# Adafruit_SPA06-003_Temperature_Pressure_.net
KiCad netlist of a schematic drawn in EAGLE
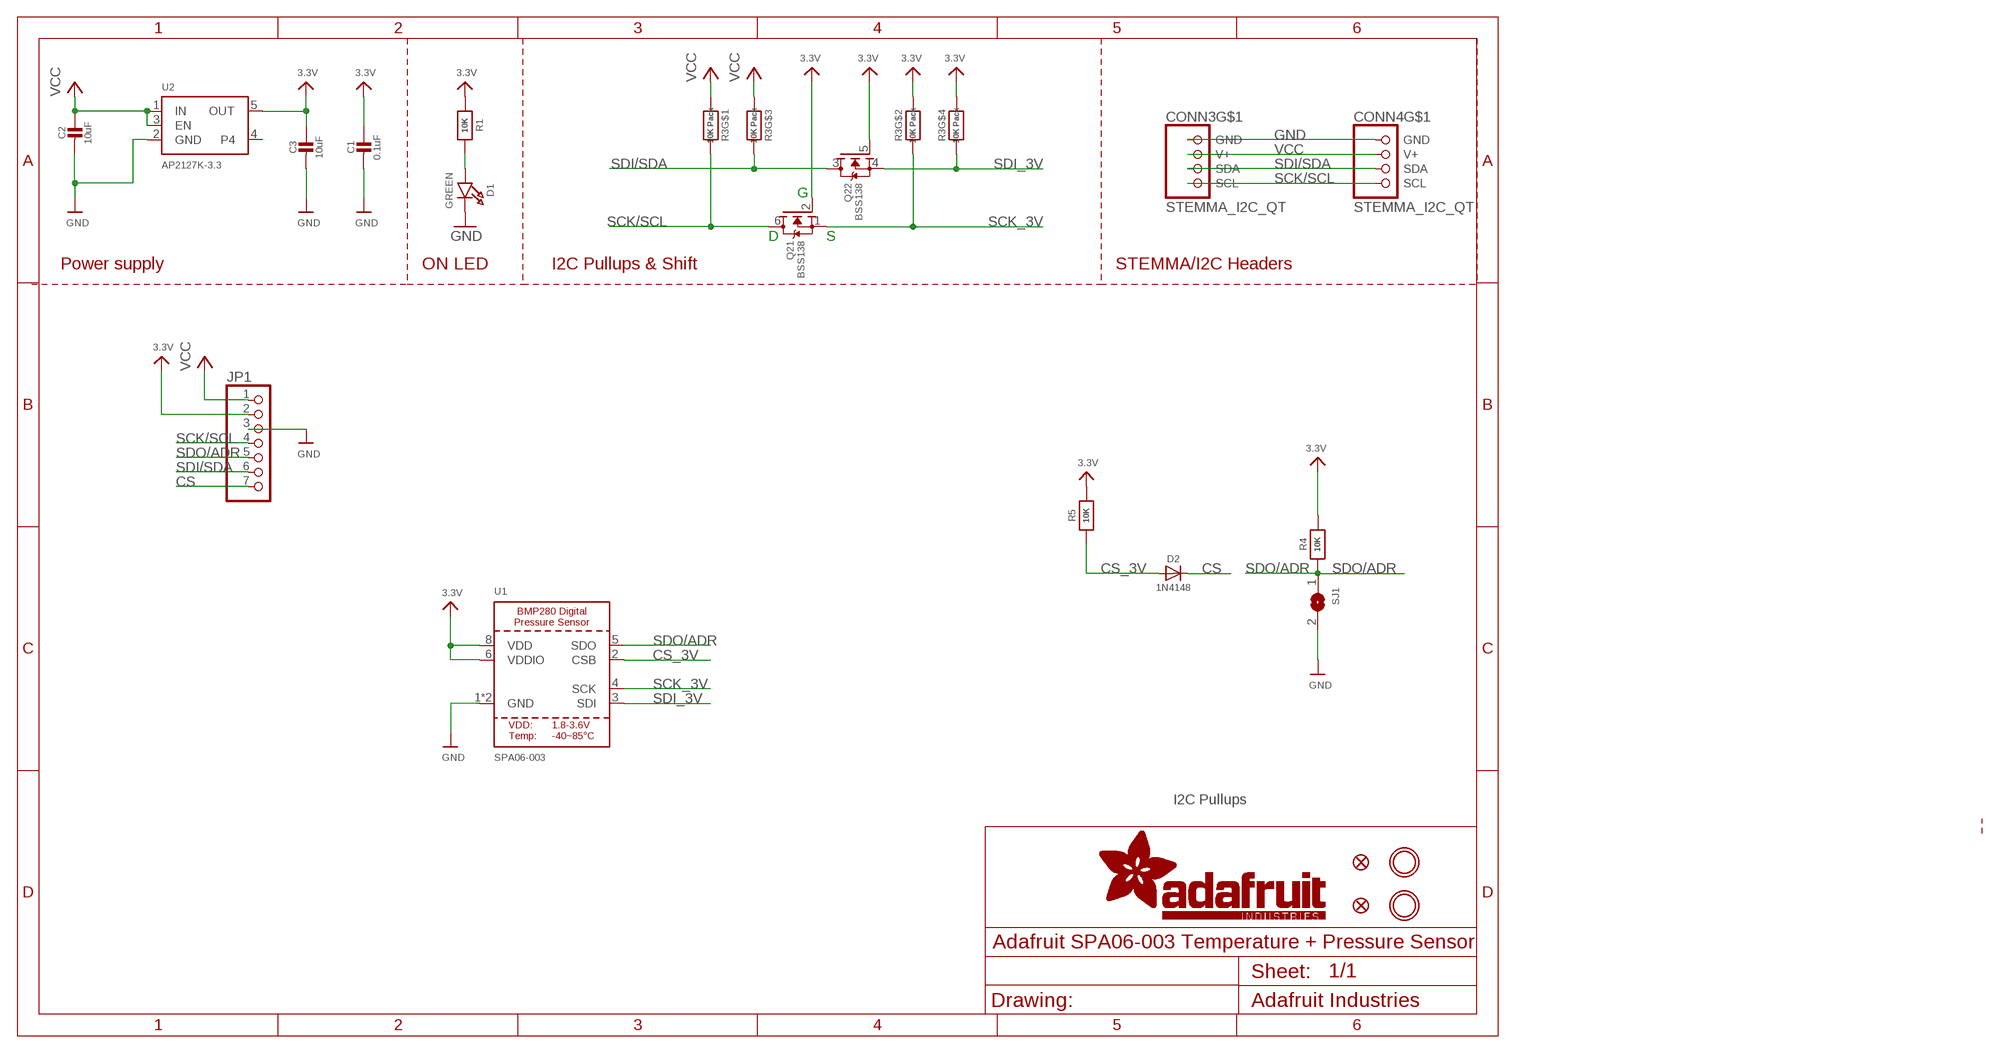
[diagram p0: schematic, sheet 1]

(export (version "E")
  (design (tool "Eeschema 10.0.6"))
  (components
    (comp (ref "C1")
      (value "0.1uF")
      (footprint "eagle-import:0603-NO")
      (libsource (lib "eagle-import") (part "CAP_CERAMIC0603_NO"))
    )
    (comp (ref "C2")
      (value "10uF")
      (footprint "eagle-import:0805-NO")
      (libsource (lib "eagle-import") (part "CAP_CERAMIC0805-NOOUTLINE"))
    )
    (comp (ref "C3")
      (value "10uF")
      (footprint "eagle-import:0805-NO")
      (libsource (lib "eagle-import") (part "CAP_CERAMIC0805-NOOUTLINE"))
    )
    (comp (ref "CONN3")
      (value "STEMMA_I2C_QT")
      (footprint "eagle-import:JST_SH4")
      (libsource (lib "eagle-import") (part "STEMMA_I2C_QT"))
    )
    (comp (ref "CONN4")
      (value "STEMMA_I2C_QT")
      (footprint "eagle-import:JST_SH4")
      (libsource (lib "eagle-import") (part "STEMMA_I2C_QT"))
    )
    (comp (ref "D1")
      (value "GREEN")
      (footprint "eagle-import:CHIPLED_0603_NOOUTLINE")
      (libsource (lib "eagle-import") (part "LED0603_NOOUTLINE"))
    )
    (comp (ref "D2")
      (value "1N4148")
      (footprint "eagle-import:SOD-323")
      (libsource (lib "eagle-import") (part "DIODESOD-323"))
    )
    (comp (ref "FID3")
      (value "FIDUCIAL_0.5MM")
      (footprint "eagle-import:FIDUCIAL_0.5MM")
      (libsource (lib "eagle-import") (part "FIDUCIAL_0.5MM"))
    )
    (comp (ref "FID4")
      (value "FIDUCIAL_0.5MM")
      (footprint "eagle-import:FIDUCIAL_0.5MM")
      (libsource (lib "eagle-import") (part "FIDUCIAL_0.5MM"))
    )
    (comp (ref "JP1")
      (value "HEADER-1X770MIL")
      (footprint "eagle-import:1X07_ROUND_70")
      (libsource (lib "eagle-import") (part "HEADER-1X770MIL"))
    )
    (comp (ref "Q2")
      (value "BSS138")
      (footprint "eagle-import:SOT363")
      (libsource (lib "eagle-import") (part "MOSFET-N_DUAL"))
    )
    (comp (ref "R1")
      (value "10K")
      (footprint "eagle-import:0603-NO")
      (libsource (lib "eagle-import") (part "RESISTOR_0603_NOOUT"))
    )
    (comp (ref "R3")
      (value "10K Pack")
      (footprint "eagle-import:RESPACK_4X0603")
      (libsource (lib "eagle-import") (part "RESISTOR_4PACK"))
    )
    (comp (ref "R4")
      (value "10K")
      (footprint "eagle-import:0603-NO")
      (libsource (lib "eagle-import") (part "RESISTOR_0603_NOOUT"))
    )
    (comp (ref "R5")
      (value "10K")
      (footprint "eagle-import:0603-NO")
      (libsource (lib "eagle-import") (part "RESISTOR_0603_NOOUT"))
    )
    (comp (ref "SJ1")
      (value "SOLDERJUMPER")
      (footprint "eagle-import:SOLDERJUMPER_ARROW_NOPASTE")
      (libsource (lib "eagle-import") (part "SOLDERJUMPER"))
    )
    (comp (ref "U$1")
      (value "MOUNTINGHOLE2.5")
      (footprint "eagle-import:MOUNTINGHOLE_2.5_PLATED")
      (libsource (lib "eagle-import") (part "MOUNTINGHOLE2.5"))
    )
    (comp (ref "U$17")
      (value "MOUNTINGHOLE2.5")
      (footprint "eagle-import:MOUNTINGHOLE_2.5_PLATED")
      (libsource (lib "eagle-import") (part "MOUNTINGHOLE2.5"))
    )
    (comp (ref "U1")
      (value "SPA06-003")
      (footprint "eagle-import:BMX280_COMBO")
      (libsource (lib "eagle-import") (part "BMP280_COMBO"))
    )
    (comp (ref "U2")
      (value "AP2127K-3.3")
      (footprint "eagle-import:SOT23-5")
      (libsource (lib "eagle-import") (part "VREG_SOT23-5"))
    )
  )
  (nets
    (net (code "1") (name "/CS") (class "Default")
      (node (ref "D2") (pin "C") (pinfunction "C_C") (pintype "passive"))
      (node (ref "JP1") (pin "7") (pinfunction "7_7") (pintype "passive"))
    )
    (net (code "2") (name "/CS_3V") (class "Default")
      (node (ref "D2") (pin "A") (pinfunction "A_A") (pintype "passive"))
      (node (ref "R5") (pin "1") (pinfunction "1_1") (pintype "passive"))
      (node (ref "U1") (pin "2") (pinfunction "CSB_2") (pintype "input"))
    )
    (net (code "3") (name "/SCK_3V") (class "Default")
      (node (ref "Q2") (pin "1") (pinfunction "S_1") (pintype "bidirectional"))
      (node (ref "R3") (pin "7") (pinfunction "2_7") (pintype "passive"))
      (node (ref "U1") (pin "4") (pinfunction "SCK_4") (pintype "input"))
    )
    (net (code "4") (name "/SCK{slash}SCL") (class "Default")
      (node (ref "CONN3") (pin "4") (pinfunction "SCL_4") (pintype "passive"))
      (node (ref "CONN4") (pin "4") (pinfunction "SCL_4") (pintype "passive"))
      (node (ref "JP1") (pin "4") (pinfunction "4_4") (pintype "passive"))
      (node (ref "Q2") (pin "6") (pinfunction "D_6") (pintype "bidirectional"))
      (node (ref "R3") (pin "8") (pinfunction "2_8") (pintype "passive"))
    )
    (net (code "5") (name "/SDI_3V") (class "Default")
      (node (ref "Q2") (pin "4") (pinfunction "S_4") (pintype "bidirectional"))
      (node (ref "R3") (pin "5") (pinfunction "2_5") (pintype "passive"))
      (node (ref "U1") (pin "3") (pinfunction "SDI_3") (pintype "input"))
    )
    (net (code "6") (name "/SDI{slash}SDA") (class "Default")
      (node (ref "CONN3") (pin "3") (pinfunction "SDA_3") (pintype "passive"))
      (node (ref "CONN4") (pin "3") (pinfunction "SDA_3") (pintype "passive"))
      (node (ref "JP1") (pin "6") (pinfunction "6_6") (pintype "passive"))
      (node (ref "Q2") (pin "3") (pinfunction "D_3") (pintype "bidirectional"))
      (node (ref "R3") (pin "6") (pinfunction "2_6") (pintype "passive"))
    )
    (net (code "7") (name "/SDO{slash}ADR") (class "Default")
      (node (ref "JP1") (pin "5") (pinfunction "5_5") (pintype "passive"))
      (node (ref "R4") (pin "1") (pinfunction "1_1") (pintype "passive"))
      (node (ref "SJ1") (pin "1") (pinfunction "1_1") (pintype "passive"))
      (node (ref "U1") (pin "5") (pinfunction "SDO_5") (pintype "output"))
    )
    (net (code "8") (name "3.3V") (class "Default")
      (node (ref "C1") (pin "1") (pinfunction "1_1") (pintype "passive"))
      (node (ref "C3") (pin "1") (pinfunction "1_1") (pintype "passive"))
      (node (ref "JP1") (pin "2") (pinfunction "2_2") (pintype "passive"))
      (node (ref "Q2") (pin "2") (pinfunction "G_2") (pintype "bidirectional"))
      (node (ref "Q2") (pin "5") (pinfunction "G_5") (pintype "bidirectional"))
      (node (ref "R1") (pin "1") (pinfunction "1_1") (pintype "passive"))
      (node (ref "R3") (pin "2") (pinfunction "1_2") (pintype "passive"))
      (node (ref "R3") (pin "4") (pinfunction "1_4") (pintype "passive"))
      (node (ref "R4") (pin "2") (pinfunction "2_2") (pintype "passive"))
      (node (ref "R5") (pin "2") (pinfunction "2_2") (pintype "passive"))
      (node (ref "U1") (pin "6") (pinfunction "VDDIO_6") (pintype "power_in"))
      (node (ref "U1") (pin "8") (pinfunction "VDD_8") (pintype "power_in"))
      (node (ref "U2") (pin "5") (pinfunction "OUT_5") (pintype "power_in"))
    )
    (net (code "9") (name "GND") (class "Default")
      (node (ref "C1") (pin "2") (pinfunction "2_2") (pintype "passive"))
      (node (ref "C2") (pin "2") (pinfunction "2_2") (pintype "passive"))
      (node (ref "C3") (pin "2") (pinfunction "2_2") (pintype "passive"))
      (node (ref "CONN3") (pin "1") (pinfunction "GND_1") (pintype "passive"))
      (node (ref "CONN4") (pin "1") (pinfunction "GND_1") (pintype "passive"))
      (node (ref "D1") (pin "C") (pinfunction "C_C") (pintype "passive"))
      (node (ref "JP1") (pin "3") (pinfunction "3_3") (pintype "passive"))
      (node (ref "SJ1") (pin "2") (pinfunction "2_2") (pintype "passive"))
      (node (ref "U1") (pin "1") (pinfunction "GND_1") (pintype "power_in"))
      (node (ref "U1") (pin "7") (pinfunction "GND_7") (pintype "power_in"))
      (node (ref "U2") (pin "2") (pinfunction "GND_2") (pintype "power_in"))
    )
    (net (code "10") (name "Net-(D1-PadA)") (class "Default")
      (node (ref "D1") (pin "A") (pinfunction "A_A") (pintype "passive"))
      (node (ref "R1") (pin "2") (pinfunction "2_2") (pintype "passive"))
    )
    (net (code "11") (name "VCC") (class "Default")
      (node (ref "C2") (pin "1") (pinfunction "1_1") (pintype "passive"))
      (node (ref "CONN3") (pin "2") (pinfunction "V+_2") (pintype "passive"))
      (node (ref "CONN4") (pin "2") (pinfunction "V+_2") (pintype "passive"))
      (node (ref "JP1") (pin "1") (pinfunction "1_1") (pintype "passive"))
      (node (ref "R3") (pin "1") (pinfunction "1_1") (pintype "passive"))
      (node (ref "R3") (pin "3") (pinfunction "1_3") (pintype "passive"))
      (node (ref "U2") (pin "1") (pinfunction "IN_1") (pintype "power_in"))
      (node (ref "U2") (pin "3") (pinfunction "EN_3") (pintype "input"))
    )
    (net (code "12") (name "unconnected-(U2-P4-Pad4)") (class "Default")
      (node (ref "U2") (pin "4") (pinfunction "P4_4") (pintype "bidirectional"))
    )
  )
)
